# pot.net
KiCad netlist of a schematic drawn in EAGLE
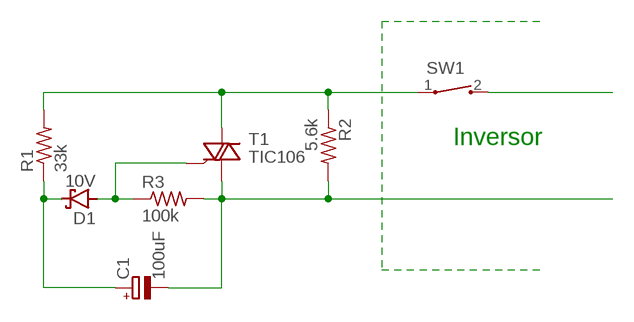
[diagram p0: schematic, sheet 1]
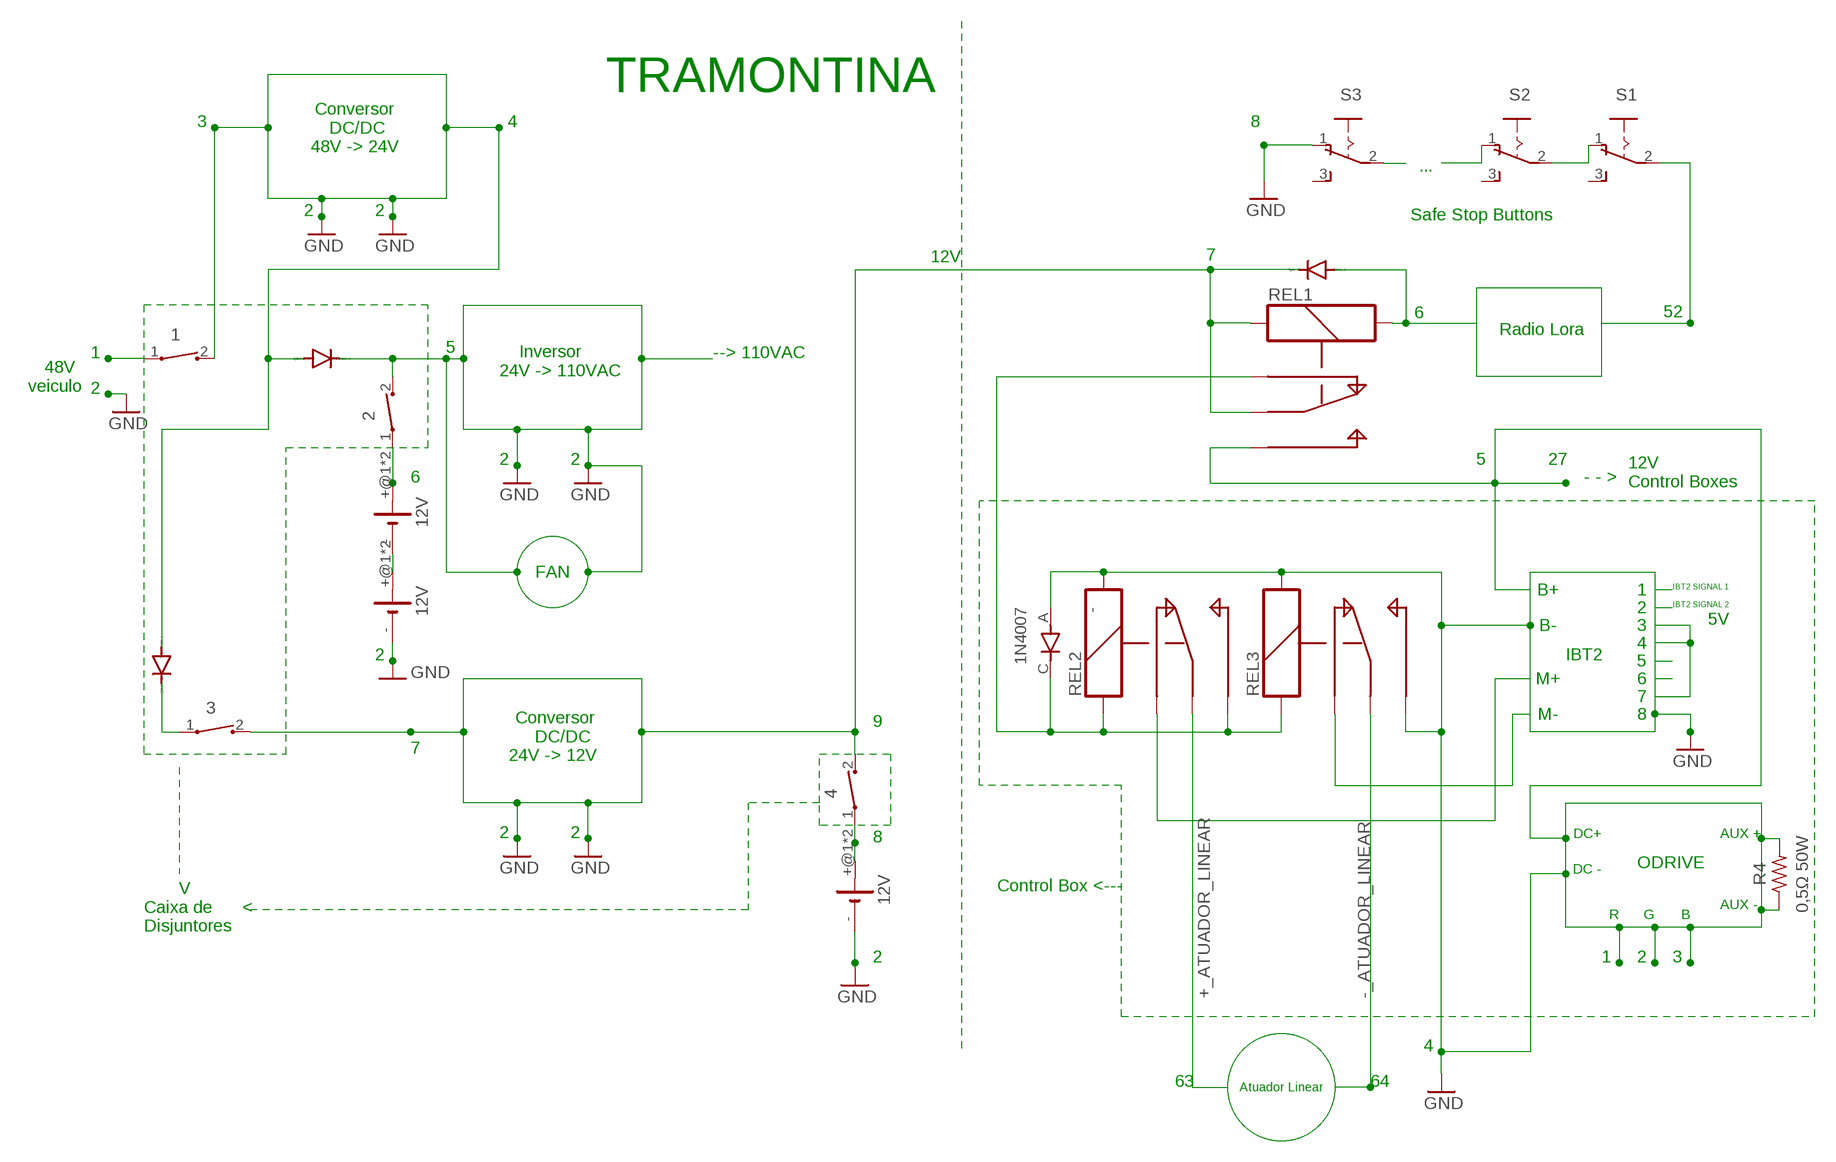
[diagram p1: schematic, sheet 2]

(export (version "E")
  (design (tool "Eeschema 10.0.6"))
  (components
    (comp (ref "-")
      (value "1N4007")
      (footprint "eagle-import:DIOAD1060W80L520D270")
      (fields (field (name "MF") "ON Semiconductor"))
      (libsource (lib "eagle-import") (part "1N4007"))
    )
    (comp (ref "1")
      (value "CT10-XXXX-A2")
      (footprint "eagle-import:CT10-XXXX-A2")
      (libsource (lib "eagle-import") (part "CT10-XXXX-A2"))
    )
    (comp (ref "2")
      (value "CT10-XXXX-A2")
      (footprint "eagle-import:CT10-XXXX-A2")
      (libsource (lib "eagle-import") (part "CT10-XXXX-A2"))
    )
    (comp (ref "3")
      (value "CT10-XXXX-A2")
      (footprint "eagle-import:CT10-XXXX-A2")
      (libsource (lib "eagle-import") (part "CT10-XXXX-A2"))
    )
    (comp (ref "4")
      (value "CT10-XXXX-A2")
      (footprint "eagle-import:CT10-XXXX-A2")
      (libsource (lib "eagle-import") (part "CT10-XXXX-A2"))
    )
    (comp (ref "D2")
      (value "1N4004")
      (footprint "eagle-import:DO41-10")
      (libsource (lib "eagle-import") (part "1N4004"))
    )
    (comp (ref "D3")
      (value "1N4004")
      (footprint "eagle-import:DO41-10")
      (libsource (lib "eagle-import") (part "1N4004"))
    )
    (comp (ref "D5")
      (value "1N4004")
      (footprint "eagle-import:DO41-10")
      (libsource (lib "eagle-import") (part "1N4004"))
    )
    (comp (ref "G1")
      (value "12V")
      (footprint "eagle-import:10MM_SM_COIN_CELL_CLIP")
      (libsource (lib "eagle-import") (part "10MM_SM_COIN_CELL_CLIP"))
    )
    (comp (ref "G2")
      (value "12V")
      (footprint "eagle-import:10MM_SM_COIN_CELL_CLIP")
      (libsource (lib "eagle-import") (part "10MM_SM_COIN_CELL_CLIP"))
    )
    (comp (ref "G3")
      (value "12V")
      (footprint "eagle-import:10MM_SM_COIN_CELL_CLIP")
      (libsource (lib "eagle-import") (part "10MM_SM_COIN_CELL_CLIP"))
    )
    (comp (ref "R4")
      (value "0,5Ω 50W")
      (footprint "eagle-import:RESAD1176W63L850D250B")
      (libsource (lib "eagle-import") (part "R-USAXIAL-11.7MM-PITCH_"))
    )
    (comp (ref "REL1")
      (value "REL-5PIN")
      (footprint "eagle-import:REL-5PIN")
      (libsource (lib "eagle-import") (part "REL-5PIN"))
    )
    (comp (ref "REL2")
      (value "REL-5PIN")
      (footprint "eagle-import:REL-5PIN")
      (libsource (lib "eagle-import") (part "REL-5PIN"))
    )
    (comp (ref "REL3")
      (value "REL-5PIN")
      (footprint "eagle-import:REL-5PIN")
      (libsource (lib "eagle-import") (part "REL-5PIN"))
    )
    (comp (ref "S1")
      (value "255SB")
      (footprint "eagle-import:255SB")
      (libsource (lib "eagle-import") (part "255SB"))
    )
    (comp (ref "S2")
      (value "255SB")
      (footprint "eagle-import:255SB")
      (libsource (lib "eagle-import") (part "255SB"))
    )
    (comp (ref "S3")
      (value "255SB")
      (footprint "eagle-import:255SB")
      (libsource (lib "eagle-import") (part "255SB"))
    )
    (comp (ref "C1")
      (value "100uF")
      (footprint "eagle-import:E2,5-7")
      (libsource (lib "eagle-import") (part "CPOL-EUE2.5-7"))
    )
    (comp (ref "D1")
      (value "10V")
      (footprint "eagle-import:DO41-7.6")
      (libsource (lib "eagle-import") (part "1N5817-B"))
    )
    (comp (ref "R1")
      (value "33k")
      (footprint "eagle-import:0204_7")
      (libsource (lib "eagle-import") (part "R-US_0204/7"))
    )
    (comp (ref "R2")
      (value "5.6k")
      (footprint "eagle-import:0204_7")
      (libsource (lib "eagle-import") (part "R-US_0204/7"))
    )
    (comp (ref "R3")
      (value "100k")
      (footprint "eagle-import:0204_7")
      (libsource (lib "eagle-import") (part "R-US_0204/7"))
    )
    (comp (ref "SW1")
      (value "CT10-XXXX-A2")
      (footprint "eagle-import:CT10-XXXX-A2")
      (libsource (lib "eagle-import") (part "CT10-XXXX-A2"))
    )
    (comp (ref "T1")
      (value "TIC106")
      (footprint "eagle-import:TO220BV")
      (libsource (lib "eagle-import") (part "TIC206D"))
    )
  )
  (nets
    (net (code "1") (name "+_ATUADOR_LINEAR") (class "Default")
      (node (ref "REL2") (pin "C") (pinfunction "C_C") (pintype "passive"))
    )
    (net (code "2") (name "-_ATUADOR_LINEAR") (class "Default")
      (node (ref "REL3") (pin "C") (pinfunction "C_C") (pintype "passive"))
    )
    (net (code "3") (name "GND") (class "Default")
      (node (ref "-") (pin "A") (pinfunction "A_A") (pintype "passive"))
      (node (ref "1") (pin "2") (pinfunction "2_2") (pintype "passive"))
      (node (ref "2") (pin "2") (pinfunction "2_2") (pintype "passive"))
      (node (ref "3") (pin "2") (pinfunction "2_2") (pintype "passive"))
      (node (ref "4") (pin "2") (pinfunction "2_2") (pintype "passive"))
      (node (ref "D2") (pin "A") (pinfunction "A_A") (pintype "passive"))
      (node (ref "D2") (pin "C") (pinfunction "C_C") (pintype "passive"))
      (node (ref "D3") (pin "A") (pinfunction "A_A") (pintype "passive"))
      (node (ref "D5") (pin "C") (pinfunction "C_C") (pintype "passive"))
      (node (ref "G2") (pin "-") (pinfunction "-_-") (pintype "passive"))
      (node (ref "G3") (pin "-") (pinfunction "-_-") (pintype "passive"))
      (node (ref "R4") (pin "1") (pinfunction "1_1") (pintype "passive"))
      (node (ref "R4") (pin "2") (pinfunction "2_2") (pintype "passive"))
      (node (ref "REL1") (pin "C") (pinfunction "C_C") (pintype "passive"))
      (node (ref "REL1") (pin "O") (pinfunction "O_O") (pintype "passive"))
      (node (ref "REL1") (pin "S1") (pinfunction "S1_S1") (pintype "passive"))
      (node (ref "REL2") (pin "S2") (pinfunction "S2_S2") (pintype "passive"))
      (node (ref "REL3") (pin "O") (pinfunction "O_O") (pintype "passive"))
      (node (ref "REL3") (pin "S2") (pinfunction "S2_S2") (pintype "passive"))
      (node (ref "S3") (pin "1") (pinfunction "O_1") (pintype "passive"))
    )
    (net (code "4") (name "Net-(--PadC)") (class "Default")
      (node (ref "-") (pin "C") (pinfunction "C_C") (pintype "passive"))
      (node (ref "REL1") (pin "S") (pinfunction "S_S") (pintype "passive"))
      (node (ref "REL2") (pin "O") (pinfunction "O_O") (pintype "passive"))
      (node (ref "REL2") (pin "S1") (pinfunction "S1_S1") (pintype "passive"))
      (node (ref "REL3") (pin "S1") (pinfunction "S1_S1") (pintype "passive"))
    )
    (net (code "5") (name "Net-(2-Pad1)") (class "Default")
      (node (ref "2") (pin "1") (pinfunction "1_1") (pintype "passive"))
      (node (ref "G1") (pin "+@1") (pinfunction "+_+@1") (pintype "passive"))
      (node (ref "G1") (pin "+@2") (pinfunction "+_+@2") (pintype "passive"))
    )
    (net (code "6") (name "Net-(3-Pad1)") (class "Default")
      (node (ref "3") (pin "1") (pinfunction "1_1") (pintype "passive"))
      (node (ref "D3") (pin "C") (pinfunction "C_C") (pintype "passive"))
    )
    (net (code "7") (name "Net-(4-Pad1)") (class "Default")
      (node (ref "4") (pin "1") (pinfunction "1_1") (pintype "passive"))
      (node (ref "G3") (pin "+@1") (pinfunction "+_+@1") (pintype "passive"))
      (node (ref "G3") (pin "+@2") (pinfunction "+_+@2") (pintype "passive"))
    )
    (net (code "8") (name "Net-(C1-Pad+)") (class "Default")
      (node (ref "C1") (pin "+") (pinfunction "+_+") (pintype "passive"))
      (node (ref "D1") (pin "C") (pinfunction "C_C") (pintype "passive"))
      (node (ref "R1") (pin "1") (pinfunction "1_1") (pintype "passive"))
    )
    (net (code "9") (name "Net-(D1-PadA)") (class "Default")
      (node (ref "D1") (pin "A") (pinfunction "A_A") (pintype "passive"))
      (node (ref "R3") (pin "1") (pinfunction "1_1") (pintype "passive"))
      (node (ref "T1") (pin "G") (pinfunction "G_G") (pintype "passive"))
    )
    (net (code "10") (name "Net-(D5-PadA)") (class "Default")
      (node (ref "D5") (pin "A") (pinfunction "A_A") (pintype "passive"))
      (node (ref "REL1") (pin "S2") (pinfunction "S2_S2") (pintype "passive"))
    )
    (net (code "11") (name "Net-(G1-Pad-)") (class "Default")
      (node (ref "G1") (pin "-") (pinfunction "-_-") (pintype "passive"))
      (node (ref "G2") (pin "+@1") (pinfunction "+_+@1") (pintype "passive"))
      (node (ref "G2") (pin "+@2") (pinfunction "+_+@2") (pintype "passive"))
    )
    (net (code "12") (name "Net-(S1-O)") (class "Default")
      (node (ref "S1") (pin "1") (pinfunction "O_1") (pintype "passive"))
      (node (ref "S2") (pin "2") (pinfunction "P_2") (pintype "passive"))
    )
    (net (code "13") (name "Net-(T1-A1)") (class "Default")
      (node (ref "C1") (pin "-") (pinfunction "-_-") (pintype "passive"))
      (node (ref "R2") (pin "2") (pinfunction "2_2") (pintype "passive"))
      (node (ref "R3") (pin "2") (pinfunction "2_2") (pintype "passive"))
      (node (ref "T1") (pin "T1") (pinfunction "A1_T1") (pintype "passive"))
    )
    (net (code "14") (name "Net-(T1-A2)") (class "Default")
      (node (ref "R1") (pin "2") (pinfunction "2_2") (pintype "passive"))
      (node (ref "R2") (pin "1") (pinfunction "1_1") (pintype "passive"))
      (node (ref "SW1") (pin "1") (pinfunction "1_1") (pintype "passive"))
      (node (ref "T1") (pin "T2") (pinfunction "A2_T2") (pintype "passive"))
    )
    (net (code "15") (name "unconnected-(1-Pad1)") (class "Default")
      (node (ref "1") (pin "1") (pinfunction "1_1") (pintype "passive"))
    )
    (net (code "16") (name "unconnected-(REL2-PadS)") (class "Default")
      (node (ref "REL2") (pin "S") (pinfunction "S_S") (pintype "passive"))
    )
    (net (code "17") (name "unconnected-(REL3-PadS)") (class "Default")
      (node (ref "REL3") (pin "S") (pinfunction "S_S") (pintype "passive"))
    )
    (net (code "18") (name "unconnected-(S1-P-Pad2)") (class "Default")
      (node (ref "S1") (pin "2") (pinfunction "P_2") (pintype "passive"))
    )
    (net (code "19") (name "unconnected-(S1-S-Pad3)") (class "Default")
      (node (ref "S1") (pin "3") (pinfunction "S_3") (pintype "passive"))
    )
    (net (code "20") (name "unconnected-(S2-O-Pad1)") (class "Default")
      (node (ref "S2") (pin "1") (pinfunction "O_1") (pintype "passive"))
    )
    (net (code "21") (name "unconnected-(S2-S-Pad3)") (class "Default")
      (node (ref "S2") (pin "3") (pinfunction "S_3") (pintype "passive"))
    )
    (net (code "22") (name "unconnected-(S3-P-Pad2)") (class "Default")
      (node (ref "S3") (pin "2") (pinfunction "P_2") (pintype "passive"))
    )
    (net (code "23") (name "unconnected-(S3-S-Pad3)") (class "Default")
      (node (ref "S3") (pin "3") (pinfunction "S_3") (pintype "passive"))
    )
    (net (code "24") (name "unconnected-(SW1-Pad2)") (class "Default")
      (node (ref "SW1") (pin "2") (pinfunction "2_2") (pintype "passive"))
    )
  )
)
